# OPEN_DRAIN_Sheet1.net
KiCad netlist of a schematic drawn in Altium Designer
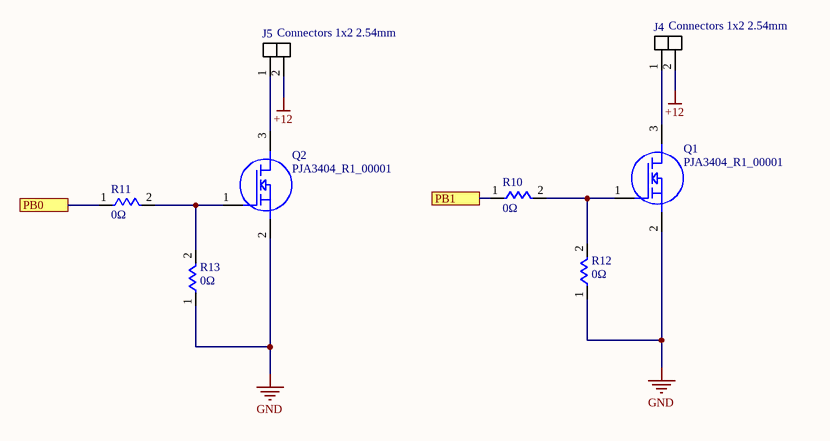
[diagram p0: OPEN_DRAIN_Sheet1.SchDoc]

(export (version "E")
  (design (tool "Eeschema 10.0.6"))
  (components
    (comp (ref "J4")
      (value "Connectors 1x2 2.54mm")
      (footprint "Connectors 1x2 2.54mm")
      (description "2 Pin (1x2) 2.54mm Erkek Pin Header THT")
      (libsource (lib "Faydali_Yuk_Schlib1") (part "Connectors 1x2 2.54mm"))
    )
    (comp (ref "J5")
      (value "Connectors 1x2 2.54mm")
      (footprint "Connectors 1x2 2.54mm")
      (description "2 Pin (1x2) 2.54mm Erkek Pin Header THT")
      (libsource (lib "Faydali_Yuk_Schlib1") (part "Connectors 1x2 2.54mm"))
    )
    (comp (ref "Q1")
      (value "PJA3404_R1_00001")
      (footprint "SOT95P240X110-3N")
      (description "PJA3404_R1_00001 - MOSFET DIS.5.6A 30V N-CH SOT23 ENHANCEMENT SMT")
      (libsource (lib "Faydali_Yuk_Schlib1") (part "Mosfet"))
    )
    (comp (ref "Q2")
      (value "PJA3404_R1_00001")
      (footprint "SOT95P240X110-3N")
      (description "PJA3404_R1_00001 - MOSFET DIS.5.6A 30V N-CH SOT23 ENHANCEMENT SMT")
      (libsource (lib "Faydali_Yuk_Schlib1") (part "Mosfet"))
    )
    (comp (ref "R10")
      (value "0Ω")
      (footprint "RES - 0603")
      (description "SMD Res")
      (libsource (lib "Faydali_Yuk_Schlib1") (part "Res"))
    )
    (comp (ref "R11")
      (value "0Ω")
      (footprint "RES - 0603")
      (description "SMD Res")
      (libsource (lib "Faydali_Yuk_Schlib1") (part "Res"))
    )
    (comp (ref "R12")
      (value "0Ω")
      (footprint "RES - 0603")
      (description "SMD Res")
      (libsource (lib "Faydali_Yuk_Schlib1") (part "Res"))
    )
    (comp (ref "R13")
      (value "0Ω")
      (footprint "RES - 0603")
      (description "SMD Res")
      (libsource (lib "Faydali_Yuk_Schlib1") (part "Res"))
    )
  )
  (nets
    (net (code "1") (name "+12") (class "Default")
      (node (ref "J4") (pin "2") (pinfunction "2_2") (pintype "passive"))
      (node (ref "J5") (pin "2") (pinfunction "2_2") (pintype "passive"))
    )
    (net (code "2") (name "/PB0") (class "Default")
      (node (ref "R11") (pin "1") (pinfunction "1_1") (pintype "passive"))
    )
    (net (code "3") (name "/PB1") (class "Default")
      (node (ref "R10") (pin "1") (pinfunction "1_1") (pintype "passive"))
    )
    (net (code "4") (name "GND") (class "Default")
      (node (ref "Q1") (pin "2") (pinfunction "2_2") (pintype "passive"))
      (node (ref "Q2") (pin "2") (pinfunction "2_2") (pintype "passive"))
      (node (ref "R12") (pin "1") (pinfunction "1_1") (pintype "passive"))
      (node (ref "R13") (pin "1") (pinfunction "1_1") (pintype "passive"))
    )
    (net (code "5") (name "Net-(J4-Pad1)") (class "Default")
      (node (ref "J4") (pin "1") (pinfunction "1_1") (pintype "passive"))
      (node (ref "Q1") (pin "3") (pinfunction "3_3") (pintype "passive"))
    )
    (net (code "6") (name "Net-(J5-Pad1)") (class "Default")
      (node (ref "J5") (pin "1") (pinfunction "1_1") (pintype "passive"))
      (node (ref "Q2") (pin "3") (pinfunction "3_3") (pintype "passive"))
    )
    (net (code "7") (name "Net-(Q1-Pad1)") (class "Default")
      (node (ref "Q1") (pin "1") (pinfunction "1_1") (pintype "passive"))
      (node (ref "R10") (pin "2") (pinfunction "2_2") (pintype "passive"))
      (node (ref "R12") (pin "2") (pinfunction "2_2") (pintype "passive"))
    )
    (net (code "8") (name "Net-(Q2-Pad1)") (class "Default")
      (node (ref "Q2") (pin "1") (pinfunction "1_1") (pintype "passive"))
      (node (ref "R11") (pin "2") (pinfunction "2_2") (pintype "passive"))
      (node (ref "R13") (pin "2") (pinfunction "2_2") (pintype "passive"))
    )
  )
)
